# Voltage_Divider_Design.net
KiCad netlist of a schematic drawn in Altium Designer
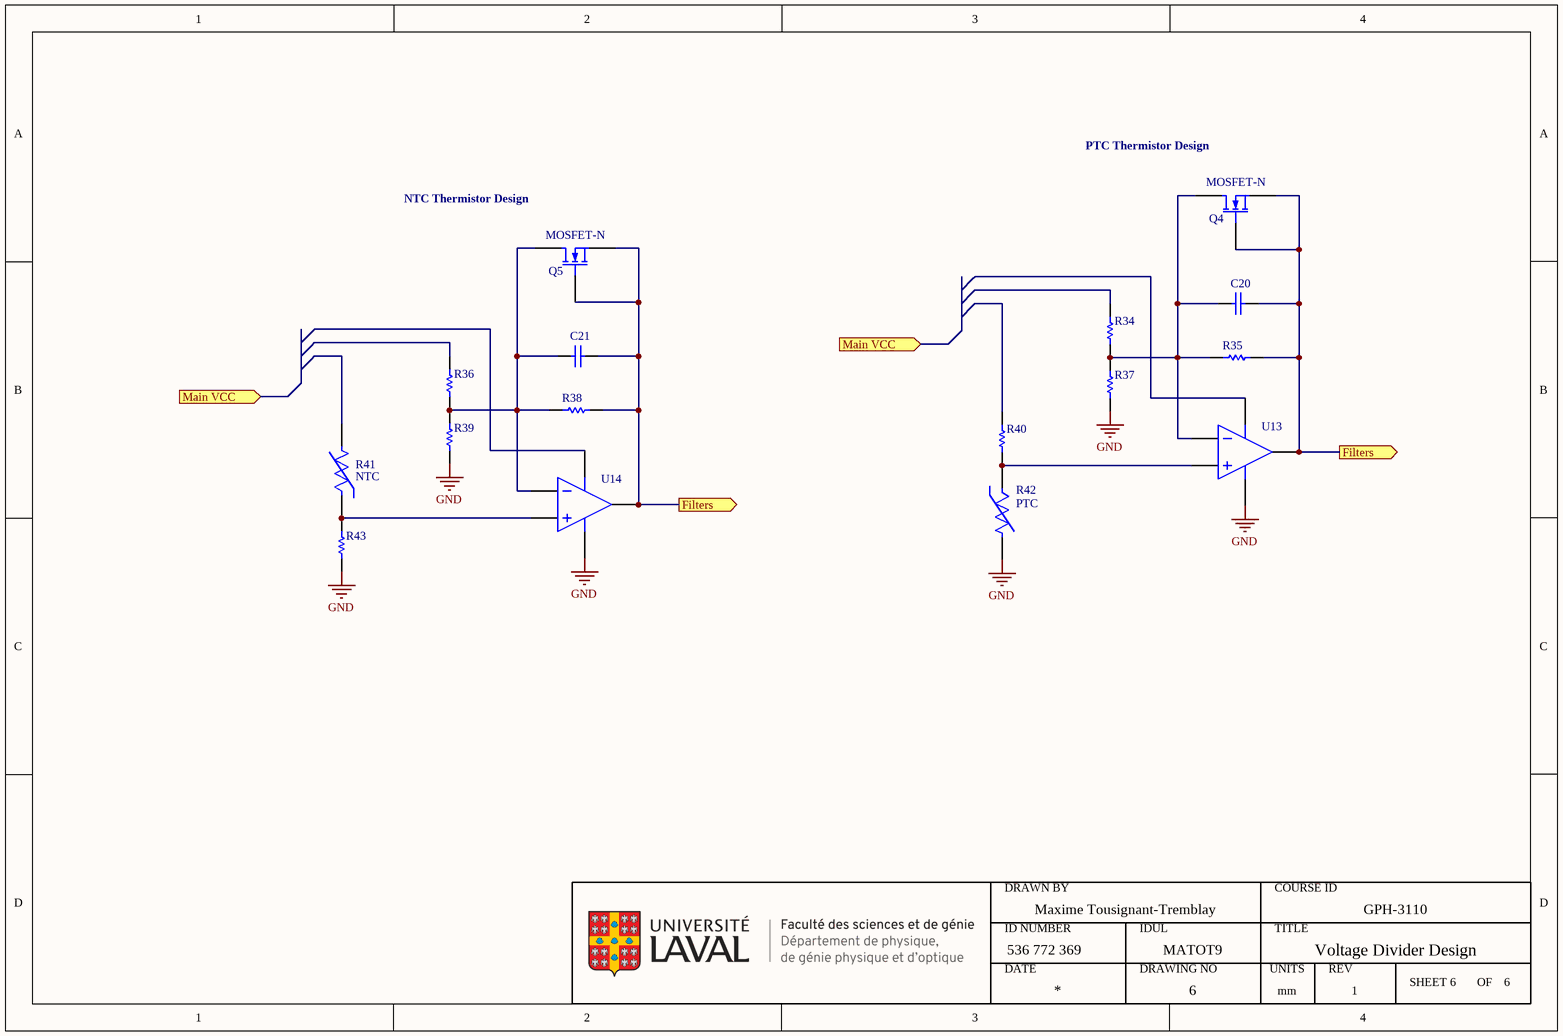
[diagram p0: Voltage Divider Design.SchDoc]

(export (version "E")
  (design (tool "Eeschema 10.0.6"))
  (components
    (comp (ref "*6")
      (value "ULaval FSG-DPGPO")
      (libsource (lib "ULaval Title Block") (part "ULaval FSG-DPGPO"))
    )
    (comp (ref "C20")
      (value "Capacitor")
      (libsource (lib "Simulation Generic Components") (part "Capacitor"))
    )
    (comp (ref "C21")
      (value "Capacitor")
      (libsource (lib "Simulation Generic Components") (part "Capacitor"))
    )
    (comp (ref "Q4")
      (value "MOSFET-N")
      (footprint "E3")
      (description "N-Channel MOSFET")
      (fields (field (name "PUBLISHER") "Altium Limited"))
      (libsource (lib "Miscellaneous Devices") (part "MOSFET-N"))
    )
    (comp (ref "Q5")
      (value "MOSFET-N")
      (footprint "E3")
      (description "N-Channel MOSFET")
      (fields (field (name "PUBLISHER") "Altium Limited"))
      (libsource (lib "Miscellaneous Devices") (part "MOSFET-N"))
    )
    (comp (ref "R34") (value "Resistor") (libsource (lib "Simulation Generic Components") (part "Resistor")))
    (comp (ref "R35") (value "Resistor") (libsource (lib "Simulation Generic Components") (part "Resistor")))
    (comp (ref "R36") (value "Resistor") (libsource (lib "Simulation Generic Components") (part "Resistor")))
    (comp (ref "R37") (value "Resistor") (libsource (lib "Simulation Generic Components") (part "Resistor")))
    (comp (ref "R38") (value "Resistor") (libsource (lib "Simulation Generic Components") (part "Resistor")))
    (comp (ref "R39") (value "Resistor") (libsource (lib "Simulation Generic Components") (part "Resistor")))
    (comp (ref "R40") (value "Resistor") (libsource (lib "Simulation Generic Components") (part "Resistor")))
    (comp (ref "R41")
      (value "NTC")
      (footprint "FP-DYA0002A-MFG")
      (libsource (lib "Laval University") (part "d90f1a9d369475ff918e5c0a1e42652"))
    )
    (comp (ref "R42")
      (value "PTC")
      (footprint "FP-DYA0002A-MFG")
      (libsource (lib "Laval University") (part "d90f1a9d369475ff918e5c0a1e42652"))
    )
    (comp (ref "R43") (value "Resistor") (libsource (lib "Simulation Generic Components") (part "Resistor")))
    (comp (ref "U13")
      (value "Ideal Operational Amplifier")
      (libsource (lib "Simulation Generic Components") (part "OpAmp with power terminals"))
    )
    (comp (ref "U14")
      (value "Ideal Operational Amplifier")
      (libsource (lib "Simulation Generic Components") (part "OpAmp with power terminals"))
    )
  )
  (nets
    (net (code "1") (name "/Filters") (class "Default")
      (node (ref "C20") (pin "2") (pinfunction "2_2") (pintype "passive"))
      (node (ref "C21") (pin "2") (pinfunction "2_2") (pintype "passive"))
      (node (ref "Q4") (pin "2") (pinfunction "G_2") (pintype "passive"))
      (node (ref "Q4") (pin "3") (pinfunction "S_3") (pintype "passive"))
      (node (ref "Q5") (pin "2") (pinfunction "G_2") (pintype "passive"))
      (node (ref "Q5") (pin "3") (pinfunction "S_3") (pintype "passive"))
      (node (ref "R35") (pin "2") (pinfunction "2_2") (pintype "passive"))
      (node (ref "R38") (pin "2") (pinfunction "2_2") (pintype "passive"))
      (node (ref "U13") (pin "3") (pinfunction "OUT_3") (pintype "passive"))
      (node (ref "U14") (pin "3") (pinfunction "OUT_3") (pintype "passive"))
    )
    (net (code "3") (name "GND") (class "Default")
      (node (ref "R37") (pin "1") (pinfunction "1_1") (pintype "passive"))
      (node (ref "R39") (pin "1") (pinfunction "1_1") (pintype "passive"))
      (node (ref "R42") (pin "1") (pinfunction "-_1") (pintype "passive"))
      (node (ref "R43") (pin "1") (pinfunction "1_1") (pintype "passive"))
      (node (ref "U13") (pin "5") (pinfunction "V-_5") (pintype "power_in"))
      (node (ref "U14") (pin "5") (pinfunction "V-_5") (pintype "power_in"))
    )
    (net (code "4") (name "Net-(Q4-D)") (class "Default")
      (node (ref "C20") (pin "1") (pinfunction "1_1") (pintype "passive"))
      (node (ref "Q4") (pin "1") (pinfunction "D_1") (pintype "passive"))
      (node (ref "R34") (pin "2") (pinfunction "2_2") (pintype "passive"))
      (node (ref "R35") (pin "1") (pinfunction "1_1") (pintype "passive"))
      (node (ref "R37") (pin "2") (pinfunction "2_2") (pintype "passive"))
      (node (ref "U13") (pin "1") (pinfunction "IN-_1") (pintype "passive"))
    )
    (net (code "5") (name "Net-(Q5-D)") (class "Default")
      (node (ref "C21") (pin "1") (pinfunction "1_1") (pintype "passive"))
      (node (ref "Q5") (pin "1") (pinfunction "D_1") (pintype "passive"))
      (node (ref "R36") (pin "2") (pinfunction "2_2") (pintype "passive"))
      (node (ref "R38") (pin "1") (pinfunction "1_1") (pintype "passive"))
      (node (ref "R39") (pin "2") (pinfunction "2_2") (pintype "passive"))
      (node (ref "U14") (pin "1") (pinfunction "IN-_1") (pintype "passive"))
    )
    (net (code "6") (name "Net-(R41-+)") (class "Default")
      (node (ref "R41") (pin "2") (pinfunction "+_2") (pintype "passive"))
      (node (ref "R43") (pin "2") (pinfunction "2_2") (pintype "passive"))
      (node (ref "U14") (pin "2") (pinfunction "IN+_2") (pintype "passive"))
    )
    (net (code "7") (name "Net-(R42-+)") (class "Default")
      (node (ref "R40") (pin "1") (pinfunction "1_1") (pintype "passive"))
      (node (ref "R42") (pin "2") (pinfunction "+_2") (pintype "passive"))
      (node (ref "U13") (pin "2") (pinfunction "IN+_2") (pintype "passive"))
    )
    (net (code "8") (name "unconnected-(R34-Pad1)") (class "Default")
      (node (ref "R34") (pin "1") (pinfunction "1_1") (pintype "passive"))
    )
    (net (code "9") (name "unconnected-(R36-Pad1)") (class "Default")
      (node (ref "R36") (pin "1") (pinfunction "1_1") (pintype "passive"))
    )
    (net (code "10") (name "unconnected-(R40-Pad2)") (class "Default")
      (node (ref "R40") (pin "2") (pinfunction "2_2") (pintype "passive"))
    )
    (net (code "11") (name "unconnected-(R41---Pad1)") (class "Default")
      (node (ref "R41") (pin "1") (pinfunction "-_1") (pintype "passive"))
    )
    (net (code "12") (name "unconnected-(U13-V+-Pad4)") (class "Default")
      (node (ref "U13") (pin "4") (pinfunction "V+_4") (pintype "power_in"))
    )
    (net (code "13") (name "unconnected-(U14-V+-Pad4)") (class "Default")
      (node (ref "U14") (pin "4") (pinfunction "V+_4") (pintype "power_in"))
    )
  )
)
